# Rasp.net
KiCad netlist of a schematic drawn in Altium Designer
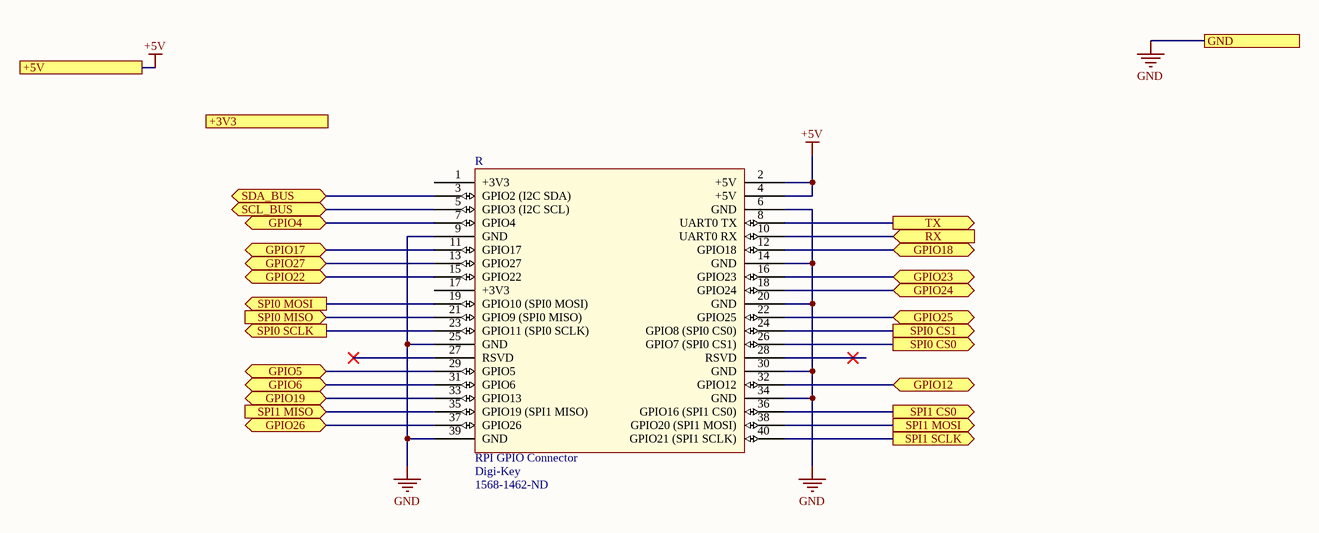
[diagram p0: Rasp.SchDoc]

(export (version "E")
  (design (tool "Eeschema 10.0.6"))
  (components
    (comp (ref "R")
      (value "RPI GPIO Connector")
      (footprint "rpi")
      (description "GPIO Header for Raspberry Pi A+/B+/Pi 2/Pi 3 - 2x20")
      (fields
        (field (name "MANUFACTURER") "SparkFun Electronics")
        (field (name "MANUFACTURER PART NUMBER") "PRT-14017")
        (field (name "SUPPLIER 1") "Digi-Key")
        (field (name "SUPPLIER PART NUMBER 1") "1568-1462-ND")
      )
      (libsource (lib "rpi") (part "rpi connector"))
    )
  )
  (nets
    (net (code "1") (name "+5V") (class "Default")
      (node (ref "R") (pin "2") (pinfunction "+5V_2") (pintype "power_in"))
      (node (ref "R") (pin "4") (pinfunction "+5V_4") (pintype "power_in"))
    )
    (net (code "3") (name "/GPIO4") (class "Default")
      (node (ref "R") (pin "7") (pinfunction "GPIO4_7") (pintype "bidirectional"))
    )
    (net (code "4") (name "/GPIO5") (class "Default")
      (node (ref "R") (pin "29") (pinfunction "GPIO5_29") (pintype "bidirectional"))
    )
    (net (code "5") (name "/GPIO6") (class "Default")
      (node (ref "R") (pin "31") (pinfunction "GPIO6_31") (pintype "bidirectional"))
    )
    (net (code "6") (name "/GPIO12") (class "Default")
      (node (ref "R") (pin "32") (pinfunction "GPIO12_32") (pintype "bidirectional"))
    )
    (net (code "7") (name "/GPIO17") (class "Default")
      (node (ref "R") (pin "11") (pinfunction "GPIO17_11") (pintype "bidirectional"))
    )
    (net (code "8") (name "/GPIO18") (class "Default")
      (node (ref "R") (pin "12") (pinfunction "GPIO18_12") (pintype "bidirectional"))
    )
    (net (code "9") (name "/GPIO19") (class "Default")
      (node (ref "R") (pin "33") (pinfunction "GPIO13_33") (pintype "bidirectional"))
    )
    (net (code "10") (name "/GPIO22") (class "Default")
      (node (ref "R") (pin "15") (pinfunction "GPIO22_15") (pintype "bidirectional"))
    )
    (net (code "11") (name "/GPIO23") (class "Default")
      (node (ref "R") (pin "16") (pinfunction "GPIO23_16") (pintype "bidirectional"))
    )
    (net (code "12") (name "/GPIO24") (class "Default")
      (node (ref "R") (pin "18") (pinfunction "GPIO24_18") (pintype "bidirectional"))
    )
    (net (code "13") (name "/GPIO25") (class "Default")
      (node (ref "R") (pin "22") (pinfunction "GPIO25_22") (pintype "bidirectional"))
    )
    (net (code "14") (name "/GPIO26") (class "Default")
      (node (ref "R") (pin "37") (pinfunction "GPIO26_37") (pintype "bidirectional"))
    )
    (net (code "15") (name "/GPIO27") (class "Default")
      (node (ref "R") (pin "13") (pinfunction "GPIO27_13") (pintype "bidirectional"))
    )
    (net (code "16") (name "/RX") (class "Default")
      (node (ref "R") (pin "10") (pinfunction "UART0_RX_10") (pintype "bidirectional"))
    )
    (net (code "17") (name "/SCL_BUS") (class "Default")
      (node (ref "R") (pin "5") (pinfunction "GPIO3_(I2C_SCL)_5") (pintype "bidirectional"))
    )
    (net (code "18") (name "/SDA_BUS") (class "Default")
      (node (ref "R") (pin "3") (pinfunction "GPIO2_(I2C_SDA)_3") (pintype "bidirectional"))
    )
    (net (code "19") (name "/SPI0 CS0") (class "Default")
      (node (ref "R") (pin "26") (pinfunction "GPIO7_(SPI0_CS1)_26") (pintype "bidirectional"))
    )
    (net (code "20") (name "/SPI0 CS1") (class "Default")
      (node (ref "R") (pin "24") (pinfunction "GPIO8_(SPI0_CS0)_24") (pintype "bidirectional"))
    )
    (net (code "21") (name "/SPI0 MISO") (class "Default")
      (node (ref "R") (pin "21") (pinfunction "GPIO9_(SPI0_MISO)_21") (pintype "bidirectional"))
    )
    (net (code "22") (name "/SPI0 MOSI") (class "Default")
      (node (ref "R") (pin "19") (pinfunction "GPIO10_(SPI0_MOSI)_19") (pintype "bidirectional"))
    )
    (net (code "23") (name "/SPI0 SCLK") (class "Default")
      (node (ref "R") (pin "23") (pinfunction "GPIO11_(SPI0_SCLK)_23") (pintype "bidirectional"))
    )
    (net (code "24") (name "/SPI1 CS0") (class "Default")
      (node (ref "R") (pin "36") (pinfunction "GPIO16_(SPI1_CS0)_36") (pintype "bidirectional"))
    )
    (net (code "25") (name "/SPI1 MISO") (class "Default")
      (node (ref "R") (pin "35") (pinfunction "GPIO19_(SPI1_MISO)_35") (pintype "bidirectional"))
    )
    (net (code "26") (name "/SPI1 MOSI") (class "Default")
      (node (ref "R") (pin "38") (pinfunction "GPIO20_(SPI1_MOSI)_38") (pintype "bidirectional"))
    )
    (net (code "27") (name "/SPI1 SCLK") (class "Default")
      (node (ref "R") (pin "40") (pinfunction "GPIO21_(SPI1_SCLK)_40") (pintype "bidirectional"))
    )
    (net (code "28") (name "/TX") (class "Default")
      (node (ref "R") (pin "8") (pinfunction "UART0_TX_8") (pintype "bidirectional"))
    )
    (net (code "29") (name "GND") (class "Default")
      (node (ref "R") (pin "14") (pinfunction "GND_14") (pintype "power_in"))
      (node (ref "R") (pin "20") (pinfunction "GND_20") (pintype "power_in"))
      (node (ref "R") (pin "25") (pinfunction "GND_25") (pintype "power_in"))
      (node (ref "R") (pin "30") (pinfunction "GND_30") (pintype "power_in"))
      (node (ref "R") (pin "34") (pinfunction "GND_34") (pintype "passive"))
      (node (ref "R") (pin "39") (pinfunction "GND_39") (pintype "power_in"))
      (node (ref "R") (pin "6") (pinfunction "GND_6") (pintype "power_in"))
      (node (ref "R") (pin "9") (pinfunction "GND_9") (pintype "power_in"))
    )
    (net (code "30") (name "unconnected-(R-+3V3-Pad1)") (class "Default")
      (node (ref "R") (pin "1") (pinfunction "+3V3_1") (pintype "power_in"))
    )
    (net (code "31") (name "unconnected-(R-+3V3-Pad17)") (class "Default")
      (node (ref "R") (pin "17") (pinfunction "+3V3_17") (pintype "power_in"))
    )
    (net (code "32") (name "unconnected-(R-RSVD-Pad27)") (class "Default")
      (node (ref "R") (pin "27") (pinfunction "RSVD_27") (pintype "passive+no_connect"))
    )
    (net (code "33") (name "unconnected-(R-RSVD-Pad28)") (class "Default")
      (node (ref "R") (pin "28") (pinfunction "RSVD_28") (pintype "passive"))
    )
  )
)
